# EURO_MIXER_2.net
KiCad netlist of a schematic drawn in EAGLE
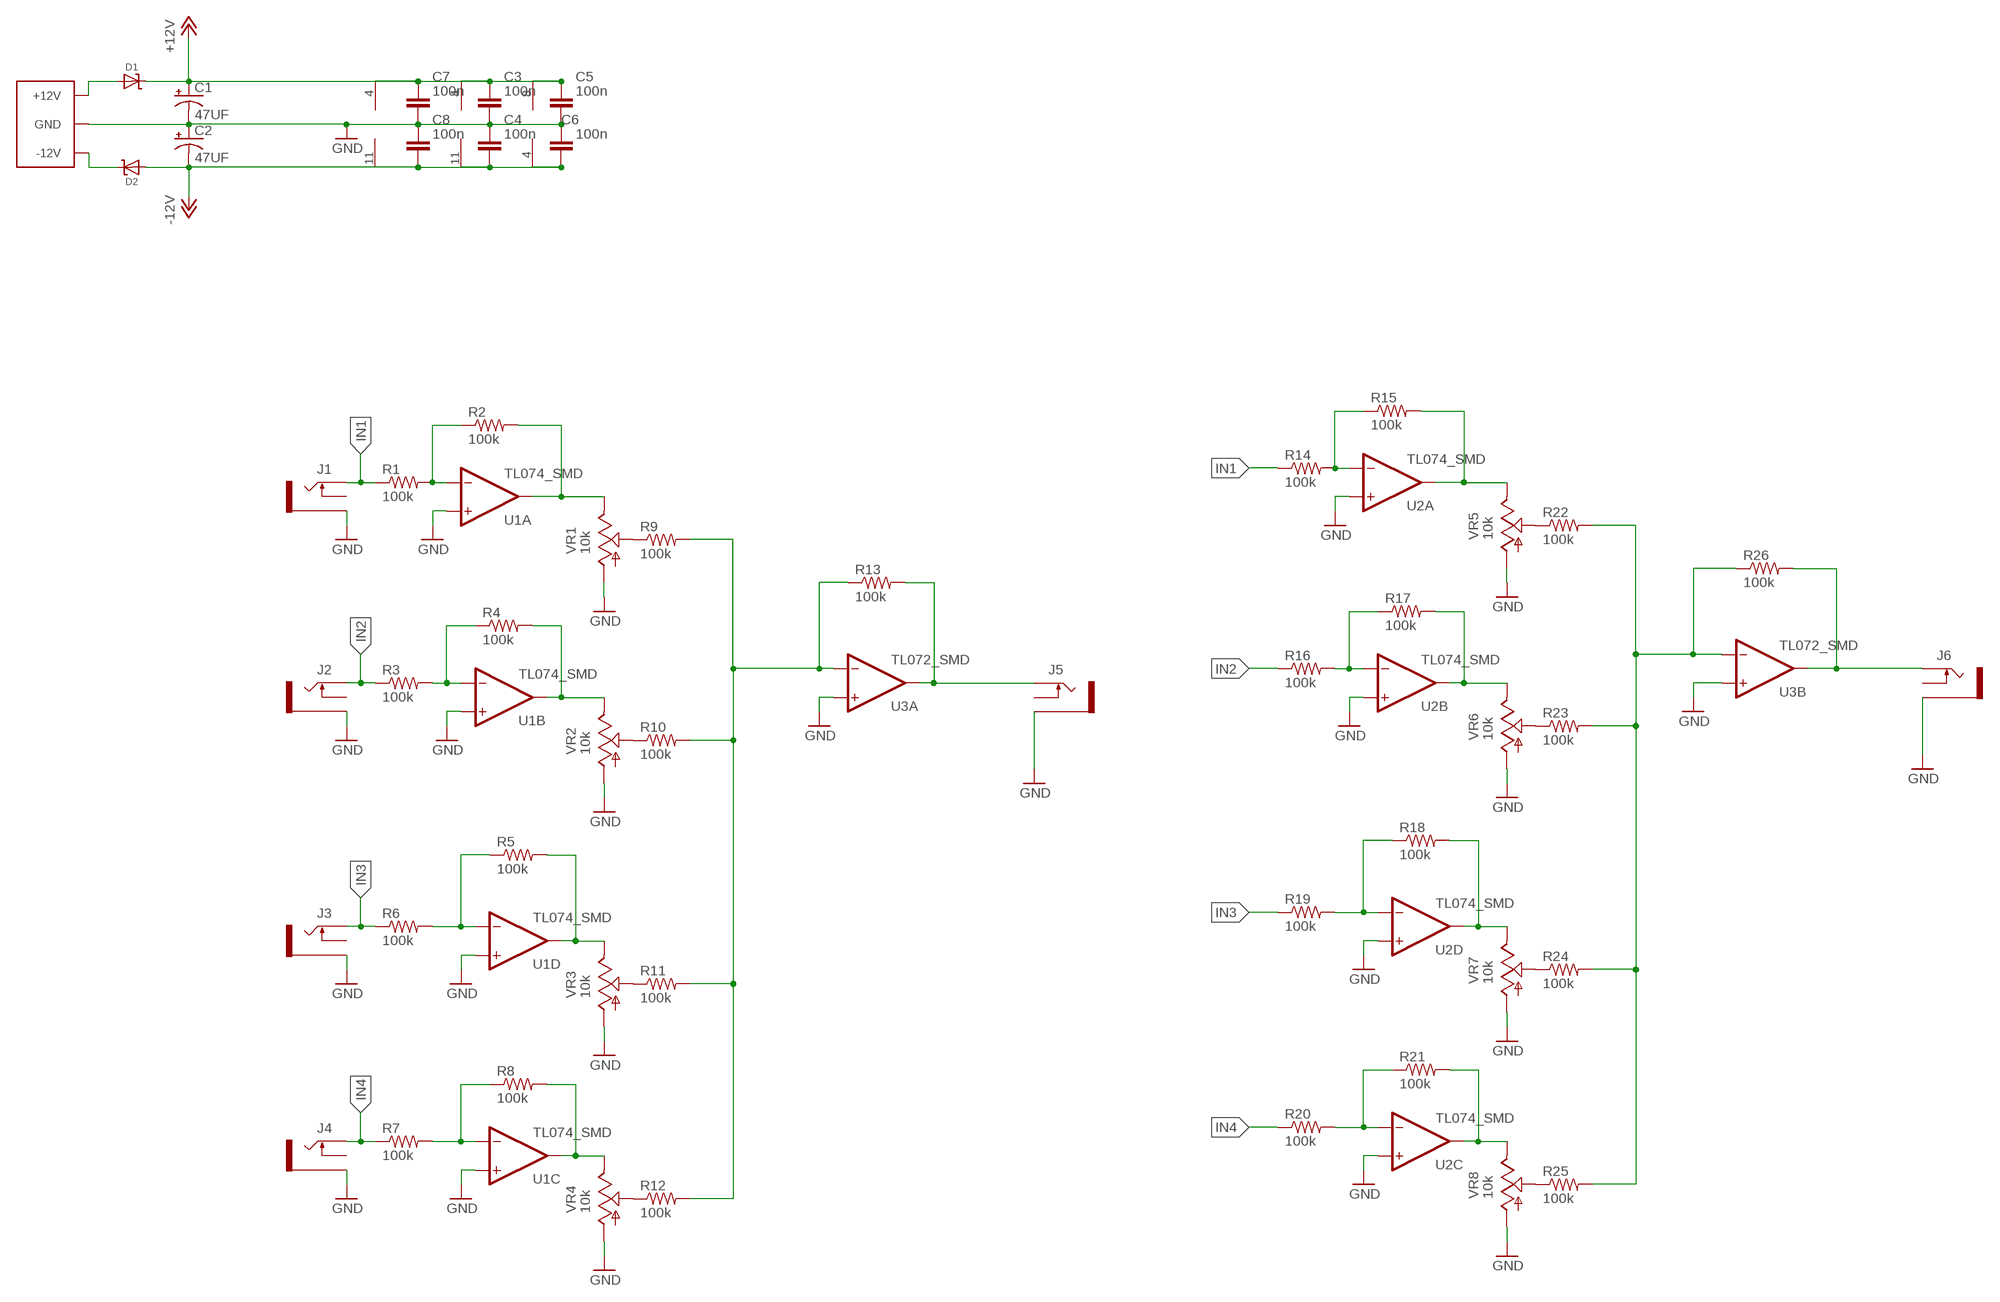
[diagram p0: schematic, sheet 1]

(export (version "E")
  (design (tool "Eeschema 10.0.6"))
  (components
    (comp (ref "C1")
      (value "47UF")
      (footprint "eagle-import:PANASONIC_D")
      (libsource (lib "eagle-import") (part "47UF-POLAR-PANASONIC_D-50V-20%"))
    )
    (comp (ref "C2")
      (value "47UF")
      (footprint "eagle-import:PANASONIC_D")
      (libsource (lib "eagle-import") (part "47UF-POLAR-PANASONIC_D-50V-20%"))
    )
    (comp (ref "C3")
      (value "100n")
      (footprint "eagle-import:CAPC2012X110")
      (libsource (lib "eagle-import") (part "CCHIP-0805(2012-METRIC)_"))
    )
    (comp (ref "C4")
      (value "100n")
      (footprint "eagle-import:CAPC2012X110")
      (libsource (lib "eagle-import") (part "CCHIP-0805(2012-METRIC)_"))
    )
    (comp (ref "C5")
      (value "100n")
      (footprint "eagle-import:CAPC2012X110")
      (libsource (lib "eagle-import") (part "CCHIP-0805(2012-METRIC)_"))
    )
    (comp (ref "C6")
      (value "100n")
      (footprint "eagle-import:CAPC2012X110")
      (libsource (lib "eagle-import") (part "CCHIP-0805(2012-METRIC)_"))
    )
    (comp (ref "C7")
      (value "100n")
      (footprint "eagle-import:CAPC2012X110")
      (libsource (lib "eagle-import") (part "CCHIP-0805(2012-METRIC)_"))
    )
    (comp (ref "C8")
      (value "100n")
      (footprint "eagle-import:CAPC2012X110")
      (libsource (lib "eagle-import") (part "CCHIP-0805(2012-METRIC)_"))
    )
    (comp (ref "D1")
      (value "DIODE-SCHOTTKYSOD-123")
      (footprint "eagle-import:SOD-123")
      (libsource (lib "eagle-import") (part "DIODE-SCHOTTKYSOD-123"))
    )
    (comp (ref "D2")
      (value "DIODE-SCHOTTKYSOD-123")
      (footprint "eagle-import:SOD-123")
      (libsource (lib "eagle-import") (part "DIODE-SCHOTTKYSOD-123"))
    )
    (comp (ref "J1")
      (value "THONKICONNNEW")
      (footprint "eagle-import:WQP-PJ301M-12_JACK")
      (libsource (lib "eagle-import") (part "THONKICONNNEW"))
    )
    (comp (ref "J2")
      (value "THONKICONNNEW")
      (footprint "eagle-import:WQP-PJ301M-12_JACK")
      (libsource (lib "eagle-import") (part "THONKICONNNEW"))
    )
    (comp (ref "J3")
      (value "THONKICONNNEW")
      (footprint "eagle-import:WQP-PJ301M-12_JACK")
      (libsource (lib "eagle-import") (part "THONKICONNNEW"))
    )
    (comp (ref "J4")
      (value "THONKICONNNEW")
      (footprint "eagle-import:WQP-PJ301M-12_JACK")
      (libsource (lib "eagle-import") (part "THONKICONNNEW"))
    )
    (comp (ref "J5")
      (value "THONKICONNNEW")
      (footprint "eagle-import:WQP-PJ301M-12_JACK")
      (libsource (lib "eagle-import") (part "THONKICONNNEW"))
    )
    (comp (ref "J6")
      (value "THONKICONNNEW")
      (footprint "eagle-import:WQP-PJ301M-12_JACK")
      (libsource (lib "eagle-import") (part "THONKICONNNEW"))
    )
    (comp (ref "JP1")
      (value "EURO_POWER_LOCKSKINNY")
      (footprint "eagle-import:EURO_POWER_HEADER")
      (libsource (lib "eagle-import") (part "EURO_POWER_LOCKSKINNY"))
    )
    (comp (ref "R1")
      (value "100k")
      (footprint "eagle-import:RESC2012X65")
      (libsource (lib "eagle-import") (part "R-USCHIP-0805(2012-METRIC)_"))
    )
    (comp (ref "R2")
      (value "100k")
      (footprint "eagle-import:RESC2012X65")
      (libsource (lib "eagle-import") (part "R-USCHIP-0805(2012-METRIC)_"))
    )
    (comp (ref "R3")
      (value "100k")
      (footprint "eagle-import:RESC2012X65")
      (libsource (lib "eagle-import") (part "R-USCHIP-0805(2012-METRIC)_"))
    )
    (comp (ref "R4")
      (value "100k")
      (footprint "eagle-import:RESC2012X65")
      (libsource (lib "eagle-import") (part "R-USCHIP-0805(2012-METRIC)_"))
    )
    (comp (ref "R5")
      (value "100k")
      (footprint "eagle-import:RESC2012X65")
      (libsource (lib "eagle-import") (part "R-USCHIP-0805(2012-METRIC)_"))
    )
    (comp (ref "R6")
      (value "100k")
      (footprint "eagle-import:RESC2012X65")
      (libsource (lib "eagle-import") (part "R-USCHIP-0805(2012-METRIC)_"))
    )
    (comp (ref "R7")
      (value "100k")
      (footprint "eagle-import:RESC2012X65")
      (libsource (lib "eagle-import") (part "R-USCHIP-0805(2012-METRIC)_"))
    )
    (comp (ref "R8")
      (value "100k")
      (footprint "eagle-import:RESC2012X65")
      (libsource (lib "eagle-import") (part "R-USCHIP-0805(2012-METRIC)_"))
    )
    (comp (ref "R9")
      (value "100k")
      (footprint "eagle-import:RESC2012X65")
      (libsource (lib "eagle-import") (part "R-USCHIP-0805(2012-METRIC)_"))
    )
    (comp (ref "R10")
      (value "100k")
      (footprint "eagle-import:RESC2012X65")
      (libsource (lib "eagle-import") (part "R-USCHIP-0805(2012-METRIC)_"))
    )
    (comp (ref "R11")
      (value "100k")
      (footprint "eagle-import:RESC2012X65")
      (libsource (lib "eagle-import") (part "R-USCHIP-0805(2012-METRIC)_"))
    )
    (comp (ref "R12")
      (value "100k")
      (footprint "eagle-import:RESC2012X65")
      (libsource (lib "eagle-import") (part "R-USCHIP-0805(2012-METRIC)_"))
    )
    (comp (ref "R13")
      (value "100k")
      (footprint "eagle-import:RESC2012X65")
      (libsource (lib "eagle-import") (part "R-USCHIP-0805(2012-METRIC)_"))
    )
    (comp (ref "R14")
      (value "100k")
      (footprint "eagle-import:RESC2012X65")
      (libsource (lib "eagle-import") (part "R-USCHIP-0805(2012-METRIC)_"))
    )
    (comp (ref "R15")
      (value "100k")
      (footprint "eagle-import:RESC2012X65")
      (libsource (lib "eagle-import") (part "R-USCHIP-0805(2012-METRIC)_"))
    )
    (comp (ref "R16")
      (value "100k")
      (footprint "eagle-import:RESC2012X65")
      (libsource (lib "eagle-import") (part "R-USCHIP-0805(2012-METRIC)_"))
    )
    (comp (ref "R17")
      (value "100k")
      (footprint "eagle-import:RESC2012X65")
      (libsource (lib "eagle-import") (part "R-USCHIP-0805(2012-METRIC)_"))
    )
    (comp (ref "R18")
      (value "100k")
      (footprint "eagle-import:RESC2012X65")
      (libsource (lib "eagle-import") (part "R-USCHIP-0805(2012-METRIC)_"))
    )
    (comp (ref "R19")
      (value "100k")
      (footprint "eagle-import:RESC2012X65")
      (libsource (lib "eagle-import") (part "R-USCHIP-0805(2012-METRIC)_"))
    )
    (comp (ref "R20")
      (value "100k")
      (footprint "eagle-import:RESC2012X65")
      (libsource (lib "eagle-import") (part "R-USCHIP-0805(2012-METRIC)_"))
    )
    (comp (ref "R21")
      (value "100k")
      (footprint "eagle-import:RESC2012X65")
      (libsource (lib "eagle-import") (part "R-USCHIP-0805(2012-METRIC)_"))
    )
    (comp (ref "R22")
      (value "100k")
      (footprint "eagle-import:RESC2012X65")
      (libsource (lib "eagle-import") (part "R-USCHIP-0805(2012-METRIC)_"))
    )
    (comp (ref "R23")
      (value "100k")
      (footprint "eagle-import:RESC2012X65")
      (libsource (lib "eagle-import") (part "R-USCHIP-0805(2012-METRIC)_"))
    )
    (comp (ref "R24")
      (value "100k")
      (footprint "eagle-import:RESC2012X65")
      (libsource (lib "eagle-import") (part "R-USCHIP-0805(2012-METRIC)_"))
    )
    (comp (ref "R25")
      (value "100k")
      (footprint "eagle-import:RESC2012X65")
      (libsource (lib "eagle-import") (part "R-USCHIP-0805(2012-METRIC)_"))
    )
    (comp (ref "R26")
      (value "100k")
      (footprint "eagle-import:RESC2012X65")
      (libsource (lib "eagle-import") (part "R-USCHIP-0805(2012-METRIC)_"))
    )
    (comp (ref "U1")
      (value "TL074_SMD")
      (footprint "eagle-import:SO14")
      (libsource (lib "eagle-import") (part "TL074_SMD"))
    )
    (comp (ref "U2")
      (value "TL074_SMD")
      (footprint "eagle-import:SO14")
      (libsource (lib "eagle-import") (part "TL074_SMD"))
    )
    (comp (ref "U3")
      (value "TL072_SMD")
      (footprint "eagle-import:SO08")
      (libsource (lib "eagle-import") (part "TL072_SMD"))
    )
    (comp (ref "VR1")
      (value "10k")
      (footprint "eagle-import:9MM_SNAP-IN_POT")
      (libsource (lib "eagle-import") (part "9MM_SNAP-IN_POT_"))
    )
    (comp (ref "VR2")
      (value "10k")
      (footprint "eagle-import:9MM_SNAP-IN_POT")
      (libsource (lib "eagle-import") (part "9MM_SNAP-IN_POT_"))
    )
    (comp (ref "VR3")
      (value "10k")
      (footprint "eagle-import:9MM_SNAP-IN_POT")
      (libsource (lib "eagle-import") (part "9MM_SNAP-IN_POT_"))
    )
    (comp (ref "VR4")
      (value "10k")
      (footprint "eagle-import:9MM_SNAP-IN_POT")
      (libsource (lib "eagle-import") (part "9MM_SNAP-IN_POT_"))
    )
    (comp (ref "VR5")
      (value "10k")
      (footprint "eagle-import:9MM_SNAP-IN_POT")
      (libsource (lib "eagle-import") (part "9MM_SNAP-IN_POT_"))
    )
    (comp (ref "VR6")
      (value "10k")
      (footprint "eagle-import:9MM_SNAP-IN_POT")
      (libsource (lib "eagle-import") (part "9MM_SNAP-IN_POT_"))
    )
    (comp (ref "VR7")
      (value "10k")
      (footprint "eagle-import:9MM_SNAP-IN_POT")
      (libsource (lib "eagle-import") (part "9MM_SNAP-IN_POT_"))
    )
    (comp (ref "VR8")
      (value "10k")
      (footprint "eagle-import:9MM_SNAP-IN_POT")
      (libsource (lib "eagle-import") (part "9MM_SNAP-IN_POT_"))
    )
  )
  (nets
    (net (code "1") (name "+12V") (class "Default")
      (node (ref "C1") (pin "+") (pinfunction "+_+") (pintype "passive"))
      (node (ref "C3") (pin "1") (pinfunction "1_1") (pintype "passive"))
      (node (ref "C5") (pin "1") (pinfunction "1_1") (pintype "passive"))
      (node (ref "C7") (pin "1") (pinfunction "1_1") (pintype "passive"))
      (node (ref "D1") (pin "C") (pinfunction "C_C") (pintype "passive"))
      (node (ref "U1") (pin "4") (pinfunction "V+_4") (pintype "power_in"))
      (node (ref "U2") (pin "4") (pinfunction "V+_4") (pintype "power_in"))
      (node (ref "U3") (pin "8") (pinfunction "V+_8") (pintype "power_in"))
    )
    (net (code "2") (name "-12V") (class "Default")
      (node (ref "C2") (pin "-") (pinfunction "-_-") (pintype "passive"))
      (node (ref "C4") (pin "2") (pinfunction "2_2") (pintype "passive"))
      (node (ref "C6") (pin "2") (pinfunction "2_2") (pintype "passive"))
      (node (ref "C8") (pin "2") (pinfunction "2_2") (pintype "passive"))
      (node (ref "D2") (pin "A") (pinfunction "A_A") (pintype "passive"))
      (node (ref "U1") (pin "11") (pinfunction "V-_11") (pintype "power_in"))
      (node (ref "U2") (pin "11") (pinfunction "V-_11") (pintype "power_in"))
      (node (ref "U3") (pin "4") (pinfunction "V-_4") (pintype "power_in"))
    )
    (net (code "3") (name "GND") (class "Default")
      (node (ref "C1") (pin "-") (pinfunction "-_-") (pintype "passive"))
      (node (ref "C2") (pin "+") (pinfunction "+_+") (pintype "passive"))
      (node (ref "C3") (pin "2") (pinfunction "2_2") (pintype "passive"))
      (node (ref "C4") (pin "1") (pinfunction "1_1") (pintype "passive"))
      (node (ref "C5") (pin "2") (pinfunction "2_2") (pintype "passive"))
      (node (ref "C6") (pin "1") (pinfunction "1_1") (pintype "passive"))
      (node (ref "C7") (pin "2") (pinfunction "2_2") (pintype "passive"))
      (node (ref "C8") (pin "1") (pinfunction "1_1") (pintype "passive"))
      (node (ref "J1") (pin "P$3_SLEEVE") (pinfunction "SLEEVE_P$3_SLEEVE") (pintype "passive"))
      (node (ref "J2") (pin "P$3_SLEEVE") (pinfunction "SLEEVE_P$3_SLEEVE") (pintype "passive"))
      (node (ref "J3") (pin "P$3_SLEEVE") (pinfunction "SLEEVE_P$3_SLEEVE") (pintype "passive"))
      (node (ref "J4") (pin "P$3_SLEEVE") (pinfunction "SLEEVE_P$3_SLEEVE") (pintype "passive"))
      (node (ref "J5") (pin "P$3_SLEEVE") (pinfunction "SLEEVE_P$3_SLEEVE") (pintype "passive"))
      (node (ref "J6") (pin "P$3_SLEEVE") (pinfunction "SLEEVE_P$3_SLEEVE") (pintype "passive"))
      (node (ref "JP1") (pin "3") (pinfunction "GND_3") (pintype "bidirectional"))
      (node (ref "JP1") (pin "4") (pinfunction "GND_4") (pintype "bidirectional"))
      (node (ref "JP1") (pin "5") (pinfunction "GND_5") (pintype "bidirectional"))
      (node (ref "JP1") (pin "6") (pinfunction "GND_6") (pintype "bidirectional"))
      (node (ref "JP1") (pin "7") (pinfunction "GND_7") (pintype "bidirectional"))
      (node (ref "JP1") (pin "8") (pinfunction "GND_8") (pintype "bidirectional"))
      (node (ref "U1") (pin "10") (pinfunction "+IN_10") (pintype "input"))
      (node (ref "U1") (pin "12") (pinfunction "+IN_12") (pintype "input"))
      (node (ref "U1") (pin "3") (pinfunction "+IN_3") (pintype "input"))
      (node (ref "U1") (pin "5") (pinfunction "+IN_5") (pintype "input"))
      (node (ref "U2") (pin "10") (pinfunction "+IN_10") (pintype "input"))
      (node (ref "U2") (pin "12") (pinfunction "+IN_12") (pintype "input"))
      (node (ref "U2") (pin "3") (pinfunction "+IN_3") (pintype "input"))
      (node (ref "U2") (pin "5") (pinfunction "+IN_5") (pintype "input"))
      (node (ref "U3") (pin "3") (pinfunction "+IN_3") (pintype "input"))
      (node (ref "U3") (pin "5") (pinfunction "+IN_5") (pintype "input"))
      (node (ref "VR1") (pin "1") (pinfunction "A_1") (pintype "passive"))
      (node (ref "VR2") (pin "1") (pinfunction "A_1") (pintype "passive"))
      (node (ref "VR3") (pin "1") (pinfunction "A_1") (pintype "passive"))
      (node (ref "VR4") (pin "1") (pinfunction "A_1") (pintype "passive"))
      (node (ref "VR5") (pin "1") (pinfunction "A_1") (pintype "passive"))
      (node (ref "VR6") (pin "1") (pinfunction "A_1") (pintype "passive"))
      (node (ref "VR7") (pin "1") (pinfunction "A_1") (pintype "passive"))
      (node (ref "VR8") (pin "1") (pinfunction "A_1") (pintype "passive"))
    )
    (net (code "4") (name "IN1") (class "Default")
      (node (ref "J1") (pin "P$1_TIP") (pinfunction "TIP_P$1_TIP") (pintype "passive"))
      (node (ref "R1") (pin "1") (pinfunction "1_1") (pintype "passive"))
      (node (ref "R14") (pin "1") (pinfunction "1_1") (pintype "passive"))
    )
    (net (code "5") (name "IN2") (class "Default")
      (node (ref "J2") (pin "P$1_TIP") (pinfunction "TIP_P$1_TIP") (pintype "passive"))
      (node (ref "R16") (pin "1") (pinfunction "1_1") (pintype "passive"))
      (node (ref "R3") (pin "1") (pinfunction "1_1") (pintype "passive"))
    )
    (net (code "6") (name "IN3") (class "Default")
      (node (ref "J3") (pin "P$1_TIP") (pinfunction "TIP_P$1_TIP") (pintype "passive"))
      (node (ref "R19") (pin "1") (pinfunction "1_1") (pintype "passive"))
      (node (ref "R6") (pin "1") (pinfunction "1_1") (pintype "passive"))
    )
    (net (code "7") (name "IN4") (class "Default")
      (node (ref "J4") (pin "P$1_TIP") (pinfunction "TIP_P$1_TIP") (pintype "passive"))
      (node (ref "R20") (pin "1") (pinfunction "1_1") (pintype "passive"))
      (node (ref "R7") (pin "1") (pinfunction "1_1") (pintype "passive"))
    )
    (net (code "8") (name "Net-(D1-PadA)") (class "Default")
      (node (ref "D1") (pin "A") (pinfunction "A_A") (pintype "passive"))
      (node (ref "JP1") (pin "10") (pinfunction "+12V_10") (pintype "bidirectional"))
      (node (ref "JP1") (pin "9") (pinfunction "+12V_9") (pintype "bidirectional"))
    )
    (net (code "9") (name "Net-(D2-PadC)") (class "Default")
      (node (ref "D2") (pin "C") (pinfunction "C_C") (pintype "passive"))
      (node (ref "JP1") (pin "1") (pinfunction "-12V_1") (pintype "bidirectional"))
      (node (ref "JP1") (pin "2") (pinfunction "-12V_2") (pintype "bidirectional"))
    )
    (net (code "10") (name "Net-(J5-TIP)") (class "Default")
      (node (ref "J5") (pin "P$1_TIP") (pinfunction "TIP_P$1_TIP") (pintype "passive"))
      (node (ref "R13") (pin "2") (pinfunction "2_2") (pintype "passive"))
      (node (ref "U3") (pin "1") (pinfunction "OUT_1") (pintype "output"))
    )
    (net (code "11") (name "Net-(J6-TIP)") (class "Default")
      (node (ref "J6") (pin "P$1_TIP") (pinfunction "TIP_P$1_TIP") (pintype "passive"))
      (node (ref "R26") (pin "2") (pinfunction "2_2") (pintype "passive"))
      (node (ref "U3") (pin "7") (pinfunction "OUT_7") (pintype "output"))
    )
    (net (code "12") (name "Net-(U1A--IN)") (class "Default")
      (node (ref "R1") (pin "2") (pinfunction "2_2") (pintype "passive"))
      (node (ref "R2") (pin "1") (pinfunction "1_1") (pintype "passive"))
      (node (ref "U1") (pin "2") (pinfunction "-IN_2") (pintype "input"))
    )
    (net (code "13") (name "Net-(U1A-OUT)") (class "Default")
      (node (ref "R2") (pin "2") (pinfunction "2_2") (pintype "passive"))
      (node (ref "U1") (pin "1") (pinfunction "OUT_1") (pintype "output"))
      (node (ref "VR1") (pin "3") (pinfunction "E_3") (pintype "passive"))
    )
    (net (code "14") (name "Net-(U1B--IN)") (class "Default")
      (node (ref "R3") (pin "2") (pinfunction "2_2") (pintype "passive"))
      (node (ref "R4") (pin "1") (pinfunction "1_1") (pintype "passive"))
      (node (ref "U1") (pin "6") (pinfunction "-IN_6") (pintype "input"))
    )
    (net (code "15") (name "Net-(U1B-OUT)") (class "Default")
      (node (ref "R4") (pin "2") (pinfunction "2_2") (pintype "passive"))
      (node (ref "U1") (pin "7") (pinfunction "OUT_7") (pintype "output"))
      (node (ref "VR2") (pin "3") (pinfunction "E_3") (pintype "passive"))
    )
    (net (code "16") (name "Net-(U1C--IN)") (class "Default")
      (node (ref "R7") (pin "2") (pinfunction "2_2") (pintype "passive"))
      (node (ref "R8") (pin "1") (pinfunction "1_1") (pintype "passive"))
      (node (ref "U1") (pin "9") (pinfunction "-IN_9") (pintype "input"))
    )
    (net (code "17") (name "Net-(U1C-OUT)") (class "Default")
      (node (ref "R8") (pin "2") (pinfunction "2_2") (pintype "passive"))
      (node (ref "U1") (pin "8") (pinfunction "OUT_8") (pintype "output"))
      (node (ref "VR4") (pin "3") (pinfunction "E_3") (pintype "passive"))
    )
    (net (code "18") (name "Net-(U1D--IN)") (class "Default")
      (node (ref "R5") (pin "1") (pinfunction "1_1") (pintype "passive"))
      (node (ref "R6") (pin "2") (pinfunction "2_2") (pintype "passive"))
      (node (ref "U1") (pin "13") (pinfunction "-IN_13") (pintype "input"))
    )
    (net (code "19") (name "Net-(U1D-OUT)") (class "Default")
      (node (ref "R5") (pin "2") (pinfunction "2_2") (pintype "passive"))
      (node (ref "U1") (pin "14") (pinfunction "OUT_14") (pintype "output"))
      (node (ref "VR3") (pin "3") (pinfunction "E_3") (pintype "passive"))
    )
    (net (code "20") (name "Net-(U2A--IN)") (class "Default")
      (node (ref "R14") (pin "2") (pinfunction "2_2") (pintype "passive"))
      (node (ref "R15") (pin "1") (pinfunction "1_1") (pintype "passive"))
      (node (ref "U2") (pin "2") (pinfunction "-IN_2") (pintype "input"))
    )
    (net (code "21") (name "Net-(U2A-OUT)") (class "Default")
      (node (ref "R15") (pin "2") (pinfunction "2_2") (pintype "passive"))
      (node (ref "U2") (pin "1") (pinfunction "OUT_1") (pintype "output"))
      (node (ref "VR5") (pin "3") (pinfunction "E_3") (pintype "passive"))
    )
    (net (code "22") (name "Net-(U2B--IN)") (class "Default")
      (node (ref "R16") (pin "2") (pinfunction "2_2") (pintype "passive"))
      (node (ref "R17") (pin "1") (pinfunction "1_1") (pintype "passive"))
      (node (ref "U2") (pin "6") (pinfunction "-IN_6") (pintype "input"))
    )
    (net (code "23") (name "Net-(U2B-OUT)") (class "Default")
      (node (ref "R17") (pin "2") (pinfunction "2_2") (pintype "passive"))
      (node (ref "U2") (pin "7") (pinfunction "OUT_7") (pintype "output"))
      (node (ref "VR6") (pin "3") (pinfunction "E_3") (pintype "passive"))
    )
    (net (code "24") (name "Net-(U2C--IN)") (class "Default")
      (node (ref "R20") (pin "2") (pinfunction "2_2") (pintype "passive"))
      (node (ref "R21") (pin "1") (pinfunction "1_1") (pintype "passive"))
      (node (ref "U2") (pin "9") (pinfunction "-IN_9") (pintype "input"))
    )
    (net (code "25") (name "Net-(U2C-OUT)") (class "Default")
      (node (ref "R21") (pin "2") (pinfunction "2_2") (pintype "passive"))
      (node (ref "U2") (pin "8") (pinfunction "OUT_8") (pintype "output"))
      (node (ref "VR8") (pin "3") (pinfunction "E_3") (pintype "passive"))
    )
    (net (code "26") (name "Net-(U2D--IN)") (class "Default")
      (node (ref "R18") (pin "1") (pinfunction "1_1") (pintype "passive"))
      (node (ref "R19") (pin "2") (pinfunction "2_2") (pintype "passive"))
      (node (ref "U2") (pin "13") (pinfunction "-IN_13") (pintype "input"))
    )
    (net (code "27") (name "Net-(U2D-OUT)") (class "Default")
      (node (ref "R18") (pin "2") (pinfunction "2_2") (pintype "passive"))
      (node (ref "U2") (pin "14") (pinfunction "OUT_14") (pintype "output"))
      (node (ref "VR7") (pin "3") (pinfunction "E_3") (pintype "passive"))
    )
    (net (code "28") (name "Net-(U3A--IN)") (class "Default")
      (node (ref "R10") (pin "2") (pinfunction "2_2") (pintype "passive"))
      (node (ref "R11") (pin "2") (pinfunction "2_2") (pintype "passive"))
      (node (ref "R12") (pin "2") (pinfunction "2_2") (pintype "passive"))
      (node (ref "R13") (pin "1") (pinfunction "1_1") (pintype "passive"))
      (node (ref "R9") (pin "2") (pinfunction "2_2") (pintype "passive"))
      (node (ref "U3") (pin "2") (pinfunction "-IN_2") (pintype "input"))
    )
    (net (code "29") (name "Net-(U3B--IN)") (class "Default")
      (node (ref "R22") (pin "2") (pinfunction "2_2") (pintype "passive"))
      (node (ref "R23") (pin "2") (pinfunction "2_2") (pintype "passive"))
      (node (ref "R24") (pin "2") (pinfunction "2_2") (pintype "passive"))
      (node (ref "R25") (pin "2") (pinfunction "2_2") (pintype "passive"))
      (node (ref "R26") (pin "1") (pinfunction "1_1") (pintype "passive"))
      (node (ref "U3") (pin "6") (pinfunction "-IN_6") (pintype "input"))
    )
    (net (code "30") (name "Net-(VR1-S)") (class "Default")
      (node (ref "R9") (pin "1") (pinfunction "1_1") (pintype "passive"))
      (node (ref "VR1") (pin "2") (pinfunction "S_2") (pintype "passive"))
    )
    (net (code "31") (name "Net-(VR2-S)") (class "Default")
      (node (ref "R10") (pin "1") (pinfunction "1_1") (pintype "passive"))
      (node (ref "VR2") (pin "2") (pinfunction "S_2") (pintype "passive"))
    )
    (net (code "32") (name "Net-(VR3-S)") (class "Default")
      (node (ref "R11") (pin "1") (pinfunction "1_1") (pintype "passive"))
      (node (ref "VR3") (pin "2") (pinfunction "S_2") (pintype "passive"))
    )
    (net (code "33") (name "Net-(VR4-S)") (class "Default")
      (node (ref "R12") (pin "1") (pinfunction "1_1") (pintype "passive"))
      (node (ref "VR4") (pin "2") (pinfunction "S_2") (pintype "passive"))
    )
    (net (code "34") (name "Net-(VR5-S)") (class "Default")
      (node (ref "R22") (pin "1") (pinfunction "1_1") (pintype "passive"))
      (node (ref "VR5") (pin "2") (pinfunction "S_2") (pintype "passive"))
    )
    (net (code "35") (name "Net-(VR6-S)") (class "Default")
      (node (ref "R23") (pin "1") (pinfunction "1_1") (pintype "passive"))
      (node (ref "VR6") (pin "2") (pinfunction "S_2") (pintype "passive"))
    )
    (net (code "36") (name "Net-(VR7-S)") (class "Default")
      (node (ref "R24") (pin "1") (pinfunction "1_1") (pintype "passive"))
      (node (ref "VR7") (pin "2") (pinfunction "S_2") (pintype "passive"))
    )
    (net (code "37") (name "Net-(VR8-S)") (class "Default")
      (node (ref "R25") (pin "1") (pinfunction "1_1") (pintype "passive"))
      (node (ref "VR8") (pin "2") (pinfunction "S_2") (pintype "passive"))
    )
    (net (code "38") (name "unconnected-(J1-SWITCH-PadP$2_SWITCH)") (class "Default")
      (node (ref "J1") (pin "P$2_SWITCH") (pinfunction "SWITCH_P$2_SWITCH") (pintype "passive"))
    )
    (net (code "39") (name "unconnected-(J2-SWITCH-PadP$2_SWITCH)") (class "Default")
      (node (ref "J2") (pin "P$2_SWITCH") (pinfunction "SWITCH_P$2_SWITCH") (pintype "passive"))
    )
    (net (code "40") (name "unconnected-(J3-SWITCH-PadP$2_SWITCH)") (class "Default")
      (node (ref "J3") (pin "P$2_SWITCH") (pinfunction "SWITCH_P$2_SWITCH") (pintype "passive"))
    )
    (net (code "41") (name "unconnected-(J4-SWITCH-PadP$2_SWITCH)") (class "Default")
      (node (ref "J4") (pin "P$2_SWITCH") (pinfunction "SWITCH_P$2_SWITCH") (pintype "passive"))
    )
    (net (code "42") (name "unconnected-(J5-SWITCH-PadP$2_SWITCH)") (class "Default")
      (node (ref "J5") (pin "P$2_SWITCH") (pinfunction "SWITCH_P$2_SWITCH") (pintype "passive"))
    )
    (net (code "43") (name "unconnected-(J6-SWITCH-PadP$2_SWITCH)") (class "Default")
      (node (ref "J6") (pin "P$2_SWITCH") (pinfunction "SWITCH_P$2_SWITCH") (pintype "passive"))
    )
  )
)
